# Light_Sensor.net
KiCad netlist of a schematic drawn in EAGLE
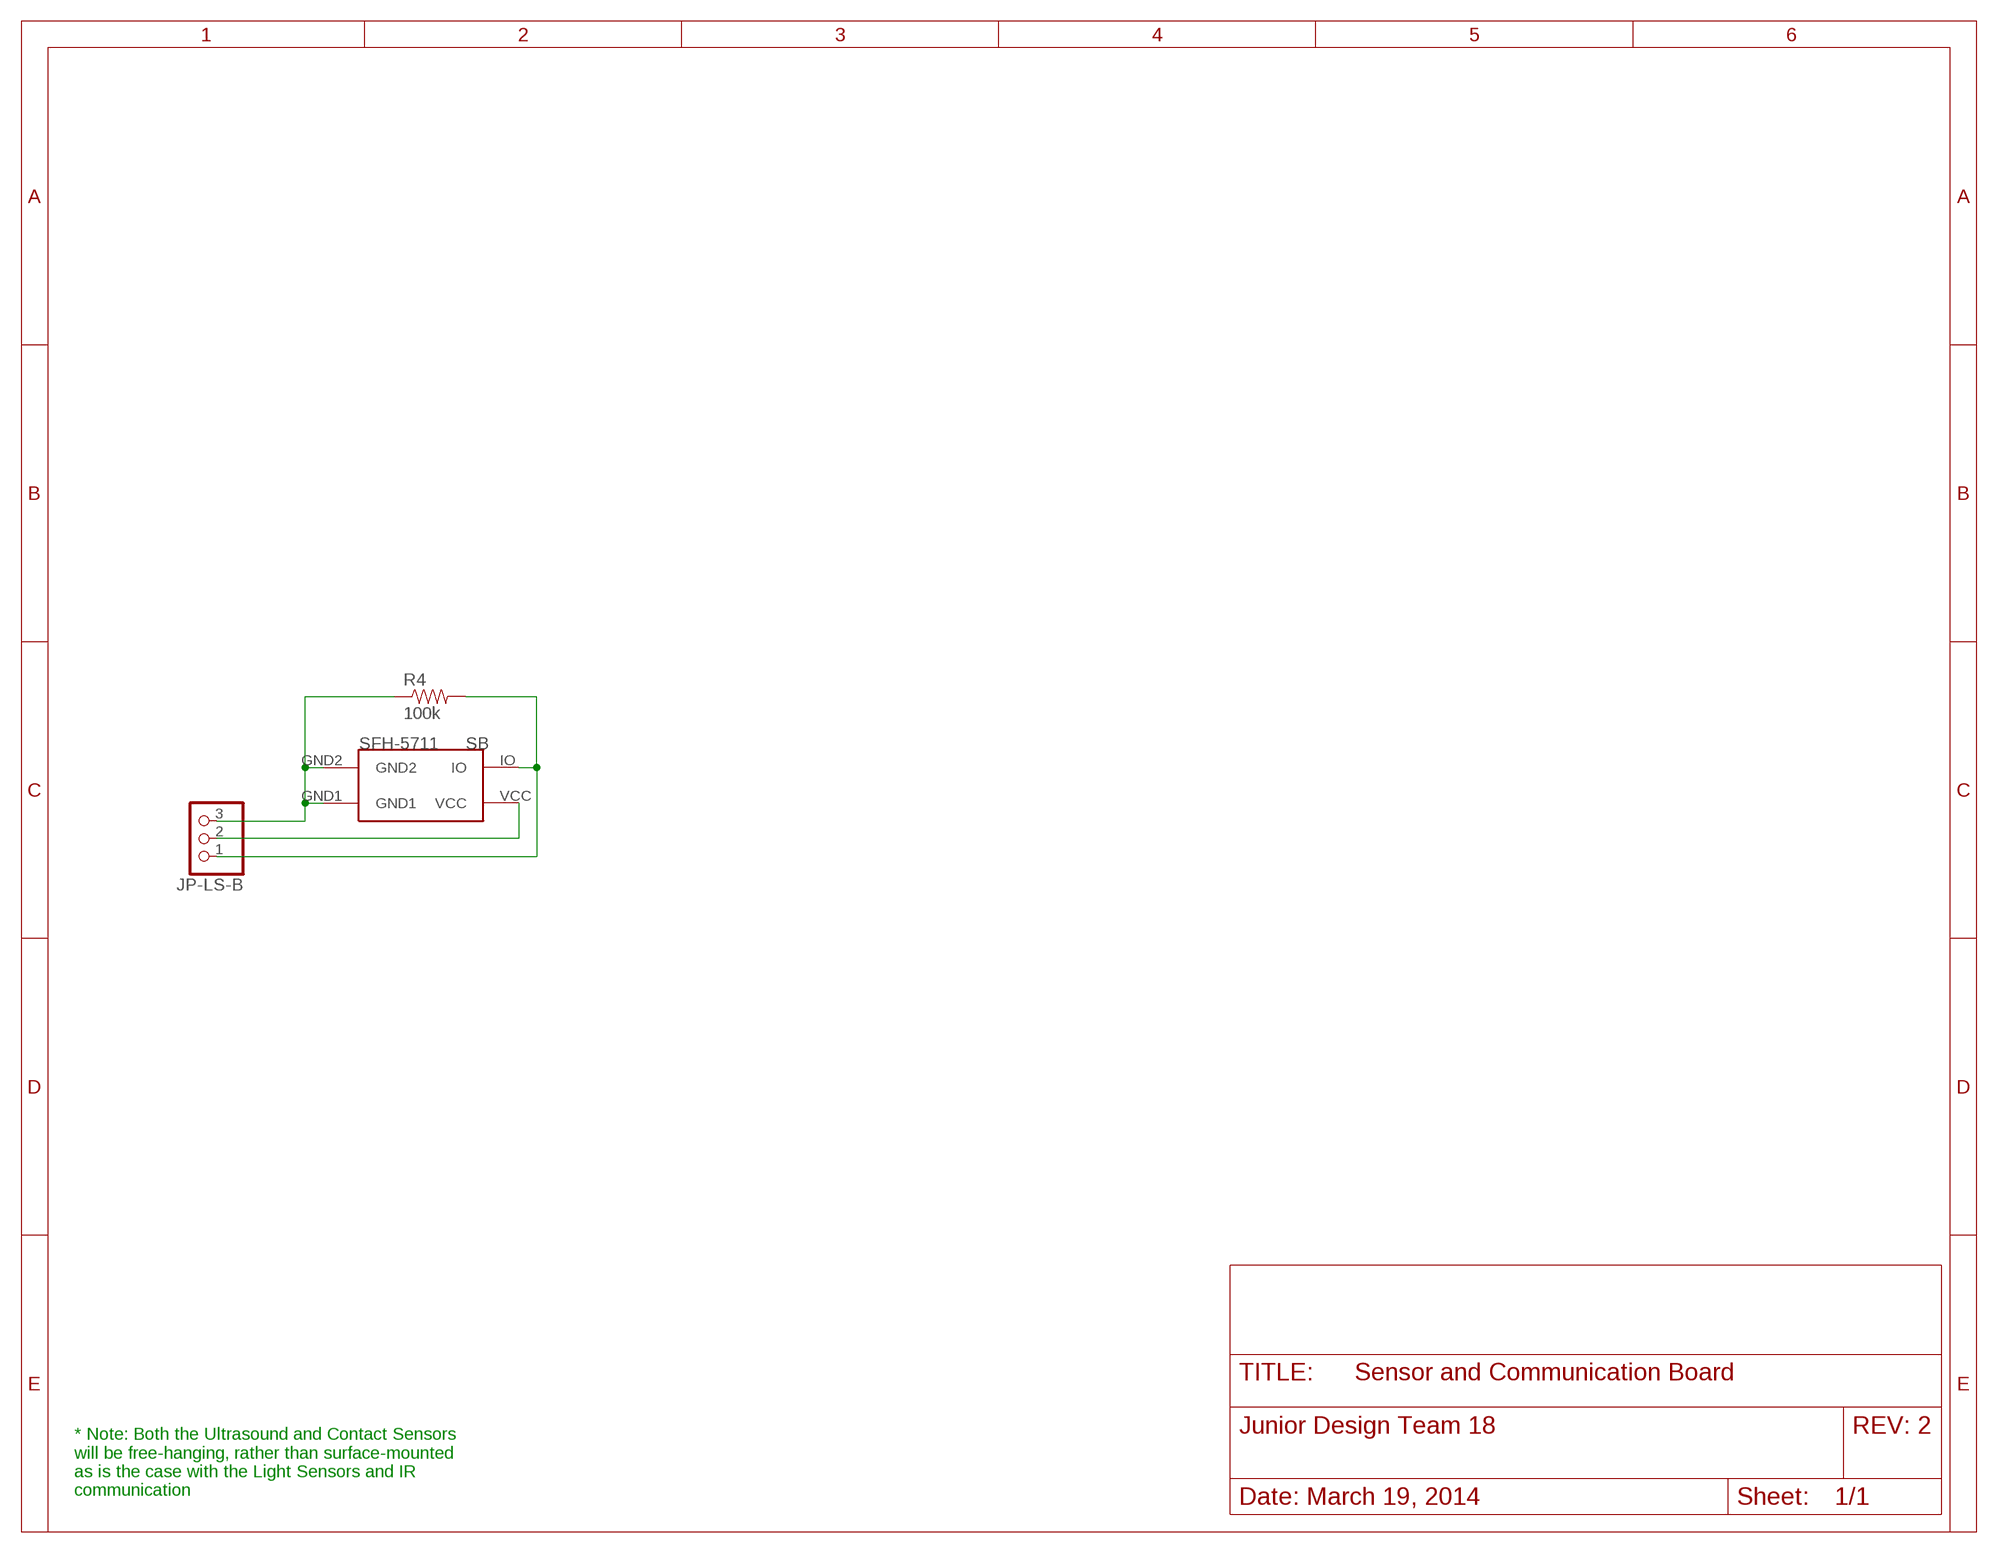
[diagram p0: schematic, sheet 1]

(export (version "E")
  (design (tool "Eeschema 10.0.6"))
  (components
    (comp (ref "JP-LS-B")
      (value "PINHD-1X3")
      (footprint "eagle-import:1X03")
      (libsource (lib "eagle-import") (part "PINHD-1X3"))
    )
    (comp (ref "R4")
      (value "100k")
      (footprint "eagle-import:0805")
      (libsource (lib "eagle-import") (part "RESISTOR0805-RES"))
    )
    (comp (ref "SFH-5711-B")
      (value "5711")
      (footprint "eagle-import:DIODE")
      (libsource (lib "eagle-import") (part "SFH5711"))
    )
  )
  (nets
    (net (code "1") (name "Net-(JP-LS-B-Pad1)") (class "Default")
      (node (ref "JP-LS-B") (pin "1") (pinfunction "1_1") (pintype "passive"))
      (node (ref "R4") (pin "2") (pinfunction "2_2") (pintype "passive"))
      (node (ref "SFH-5711-B") (pin "IO") (pinfunction "IO_IO") (pintype "bidirectional"))
    )
    (net (code "2") (name "Net-(JP-LS-B-Pad2)") (class "Default")
      (node (ref "JP-LS-B") (pin "2") (pinfunction "2_2") (pintype "passive"))
      (node (ref "SFH-5711-B") (pin "VCC") (pinfunction "VCC_VCC") (pintype "bidirectional"))
    )
    (net (code "3") (name "Net-(JP-LS-B-Pad3)") (class "Default")
      (node (ref "JP-LS-B") (pin "3") (pinfunction "3_3") (pintype "passive"))
      (node (ref "R4") (pin "1") (pinfunction "1_1") (pintype "passive"))
      (node (ref "SFH-5711-B") (pin "GND1") (pinfunction "GND1_GND1") (pintype "bidirectional"))
      (node (ref "SFH-5711-B") (pin "GND2") (pinfunction "GND2_GND2") (pintype "bidirectional"))
    )
  )
)
